# Kasli-SOC_bank112.net
KiCad netlist of a schematic drawn in Altium Designer
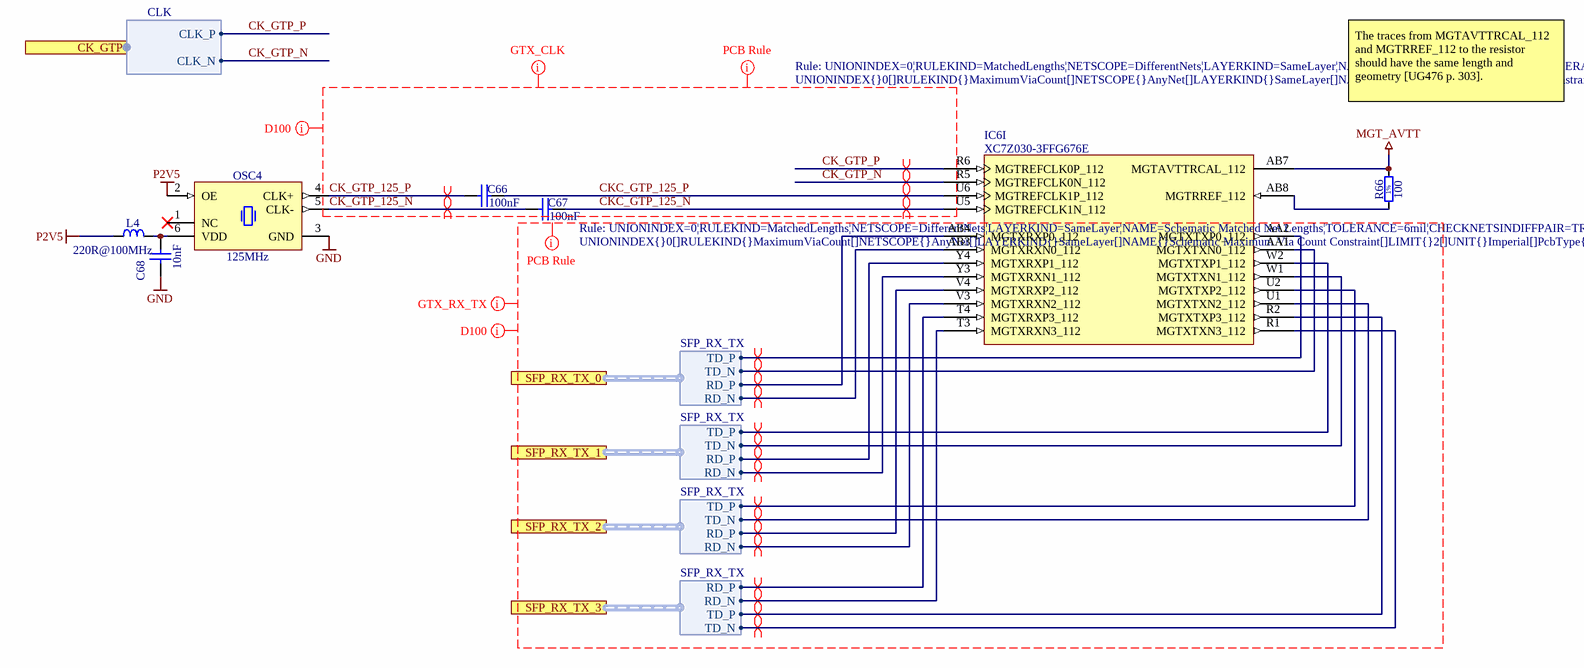
[diagram p0: Kasli-SOC_bank112.SchDoc]

(export (version "E")
  (design (tool "Eeschema 10.0.6"))
  (components
    (comp (ref "C66")
      (value "100nF")
      (footprint "CAPC0603X33N")
      (description "Non-polarised capacitor")
      (fields
        (field (name "PART NUMBER") "CC0201_100NF_6.3V_10%_X5R")
        (field (name "VOLTAGE") "6.3V")
        (field (name "AUTHOR") "CERN DEM JLC")
      )
      (libsource (lib "Capacitors") (part "Capacitor - non polarized"))
    )
    (comp (ref "C67")
      (value "100nF")
      (footprint "CAPC0603X33N")
      (description "Non-polarised capacitor")
      (fields
        (field (name "PART NUMBER") "CC0201_100NF_6.3V_10%_X5R")
        (field (name "VOLTAGE") "6.3V")
        (field (name "AUTHOR") "CERN DEM JLC")
      )
      (libsource (lib "Capacitors") (part "Capacitor - non polarized"))
    )
    (comp (ref "C68")
      (value "10nF")
      (footprint "CAPC1005X55N")
      (description "Non-polarised capacitor")
      (fields
        (field (name "PART NUMBER") "CC0402_10NF_16V_10%_X7R")
        (field (name "VOLTAGE") "16V")
        (field (name "AUTHOR") "CERN DEM JLC")
      )
      (libsource (lib "Capacitors") (part "Capacitor - non polarized"))
    )
    (comp (ref "IC6")
      (value "XC7Z030-3FFG676E")
      (footprint "BGA676C100P26X26_2700X2700X324")
      (fields (field (name "MANUFACTURER") "XILINX") (field (name "AUTHOR") "CERN DEM JLC"))
      (libsource (lib "ICs And Semiconductors") (part "XC7Z030-2FFG676I"))
    )
    (comp (ref "L4")
      (value "220R@100MHz")
      (footprint "INDC2012X105N")
      (description "Inductor")
      (fields
        (field (name "PART NUMBER") "IND0805_MURATA_BLM21PG221SN1D")
        (field (name "POWER") "2A")
        (field (name "AUTHOR") "CERN DEM JLC")
      )
      (libsource (lib "Inductors & Transformers") (part "Inductor"))
    )
    (comp (ref "OSC4")
      (value "125MHz")
      (footprint "OSC_SILICON-LAB_SI510-6N(5X7)")
      (description "Crystal Oscillator 6 pins, Si510 (LVDS/LVPECL/HCSL/Dual CMOS)")
      (fields
        (field (name "PART NUMBER") "OSC_125MHZ_SILICON-LAB_510FBA125M000AAG")
        (field (name "MANUFACTURER") "SILICON LABS")
        (field (name "AUTHOR") "CERN DEM JMW")
      )
      (libsource (lib "ICs And Semiconductors") (part "Oscillator SILICON-LAB_Si510-6N"))
    )
    (comp (ref "R66")
      (value "100")
      (footprint "RESC0603X28N")
      (description "Resistor - 1%")
      (fields
        (field (name "PART NUMBER") "R0201_100R_1%_0.05W_200PPM")
        (field (name "POWER") "0.05W")
        (field (name "AUTHOR") "CERN DEM JLC")
      )
      (libsource (lib "Resistors") (part "Resistor - 1%"))
    )
  )
  (nets
    (net (code "3") (name "/CKC_GTP_125_N") (class "Default")
      (node (ref "C67") (pin "2") (pinfunction "2_2") (pintype "passive"))
      (node (ref "IC6") (pin "U5") (pinfunction "MGTREFCLK1N_112_U5") (pintype "input"))
    )
    (net (code "4") (name "/CKC_GTP_125_P") (class "Default")
      (node (ref "C66") (pin "2") (pinfunction "2_2") (pintype "passive"))
      (node (ref "IC6") (pin "U6") (pinfunction "MGTREFCLK1P_112_U6") (pintype "input"))
    )
    (net (code "5") (name "/CK_GTP_125_N") (class "Default")
      (node (ref "C67") (pin "1") (pinfunction "1_1") (pintype "passive"))
      (node (ref "OSC4") (pin "5") (pinfunction "CLK-_5") (pintype "output"))
    )
    (net (code "6") (name "/CK_GTP_125_P") (class "Default")
      (node (ref "C66") (pin "1") (pinfunction "1_1") (pintype "passive"))
      (node (ref "OSC4") (pin "4") (pinfunction "CLK+_4") (pintype "output"))
    )
    (net (code "7") (name "/CK_GTP_N") (class "Default")
      (node (ref "IC6") (pin "R5") (pinfunction "MGTREFCLK0N_112_R5") (pintype "input"))
    )
    (net (code "8") (name "/CK_GTP_P") (class "Default")
      (node (ref "IC6") (pin "R6") (pinfunction "MGTREFCLK0P_112_R6") (pintype "input"))
    )
    (net (code "11") (name "GND") (class "Default")
      (node (ref "C68") (pin "1") (pinfunction "1_1") (pintype "passive"))
      (node (ref "OSC4") (pin "3") (pinfunction "GND_3") (pintype "power_in"))
    )
    (net (code "12") (name "MGT_AVTT") (class "Default")
      (node (ref "IC6") (pin "AB7") (pinfunction "MGTAVTTRCAL_112_AB7") (pintype "passive"))
      (node (ref "R66") (pin "2") (pinfunction "2_2") (pintype "passive"))
    )
    (net (code "13") (name "Net-(IC6I-MGTRREF_112)") (class "Default")
      (node (ref "IC6") (pin "AB8") (pinfunction "MGTRREF_112_AB8") (pintype "input"))
      (node (ref "R66") (pin "1") (pinfunction "1_1") (pintype "passive"))
    )
    (net (code "14") (name "Net-(OSC4-VDD)") (class "Default")
      (node (ref "C68") (pin "2") (pinfunction "2_2") (pintype "passive"))
      (node (ref "L4") (pin "2") (pinfunction "2_2") (pintype "passive"))
      (node (ref "OSC4") (pin "6") (pinfunction "VDD_6") (pintype "power_in"))
    )
    (net (code "15") (name "P2V5") (class "Default")
      (node (ref "L4") (pin "1") (pinfunction "1_1") (pintype "passive"))
      (node (ref "OSC4") (pin "2") (pinfunction "OE_2") (pintype "input"))
    )
    (net (code "16") (name "unconnected-(IC6I-MGTXRXN0_112-PadAB3)") (class "Default")
      (node (ref "IC6") (pin "AB3") (pinfunction "MGTXRXN0_112_AB3") (pintype "input"))
    )
    (net (code "17") (name "unconnected-(IC6I-MGTXRXN1_112-PadY3)") (class "Default")
      (node (ref "IC6") (pin "Y3") (pinfunction "MGTXRXN1_112_Y3") (pintype "input"))
    )
    (net (code "18") (name "unconnected-(IC6I-MGTXRXN2_112-PadV3)") (class "Default")
      (node (ref "IC6") (pin "V3") (pinfunction "MGTXRXN2_112_V3") (pintype "input"))
    )
    (net (code "19") (name "unconnected-(IC6I-MGTXRXN3_112-PadT3)") (class "Default")
      (node (ref "IC6") (pin "T3") (pinfunction "MGTXRXN3_112_T3") (pintype "input"))
    )
    (net (code "20") (name "unconnected-(IC6I-MGTXRXP0_112-PadAB4)") (class "Default")
      (node (ref "IC6") (pin "AB4") (pinfunction "MGTXRXP0_112_AB4") (pintype "input"))
    )
    (net (code "21") (name "unconnected-(IC6I-MGTXRXP1_112-PadY4)") (class "Default")
      (node (ref "IC6") (pin "Y4") (pinfunction "MGTXRXP1_112_Y4") (pintype "input"))
    )
    (net (code "22") (name "unconnected-(IC6I-MGTXRXP2_112-PadV4)") (class "Default")
      (node (ref "IC6") (pin "V4") (pinfunction "MGTXRXP2_112_V4") (pintype "input"))
    )
    (net (code "23") (name "unconnected-(IC6I-MGTXRXP3_112-PadT4)") (class "Default")
      (node (ref "IC6") (pin "T4") (pinfunction "MGTXRXP3_112_T4") (pintype "input"))
    )
    (net (code "24") (name "unconnected-(IC6I-MGTXTXN0_112-PadAA1)") (class "Default")
      (node (ref "IC6") (pin "AA1") (pinfunction "MGTXTXN0_112_AA1") (pintype "output"))
    )
    (net (code "25") (name "unconnected-(IC6I-MGTXTXN1_112-PadW1)") (class "Default")
      (node (ref "IC6") (pin "W1") (pinfunction "MGTXTXN1_112_W1") (pintype "output"))
    )
    (net (code "26") (name "unconnected-(IC6I-MGTXTXN2_112-PadU1)") (class "Default")
      (node (ref "IC6") (pin "U1") (pinfunction "MGTXTXN2_112_U1") (pintype "output"))
    )
    (net (code "27") (name "unconnected-(IC6I-MGTXTXN3_112-PadR1)") (class "Default")
      (node (ref "IC6") (pin "R1") (pinfunction "MGTXTXN3_112_R1") (pintype "output"))
    )
    (net (code "28") (name "unconnected-(IC6I-MGTXTXP0_112-PadAA2)") (class "Default")
      (node (ref "IC6") (pin "AA2") (pinfunction "MGTXTXP0_112_AA2") (pintype "output"))
    )
    (net (code "29") (name "unconnected-(IC6I-MGTXTXP1_112-PadW2)") (class "Default")
      (node (ref "IC6") (pin "W2") (pinfunction "MGTXTXP1_112_W2") (pintype "output"))
    )
    (net (code "30") (name "unconnected-(IC6I-MGTXTXP2_112-PadU2)") (class "Default")
      (node (ref "IC6") (pin "U2") (pinfunction "MGTXTXP2_112_U2") (pintype "output"))
    )
    (net (code "31") (name "unconnected-(IC6I-MGTXTXP3_112-PadR2)") (class "Default")
      (node (ref "IC6") (pin "R2") (pinfunction "MGTXTXP3_112_R2") (pintype "output"))
    )
    (net (code "32") (name "unconnected-(OSC4-NC-Pad1)") (class "Default")
      (node (ref "OSC4") (pin "1") (pinfunction "NC_1") (pintype "passive+no_connect"))
    )
  )
)
